# Hall_sensor.net
KiCad netlist of a schematic drawn in Altium Designer
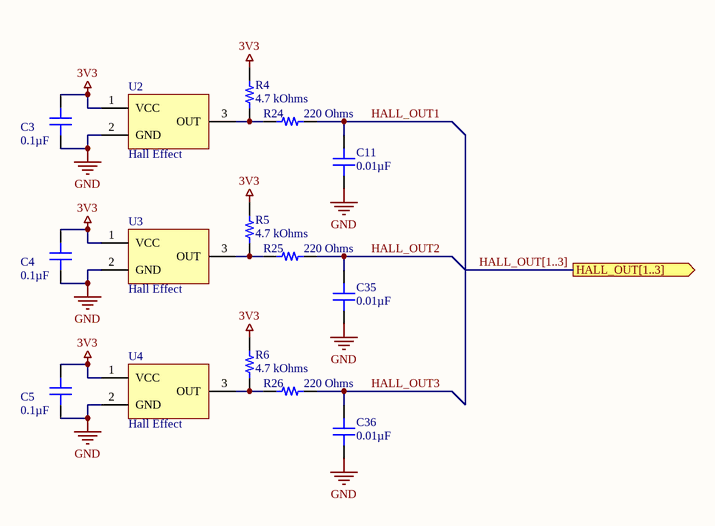
[diagram p0: Hall_sensor.SchDoc]

(export (version "E")
  (design (tool "Eeschema 10.0.6"))
  (components
    (comp (ref "C3")
      (value "0.1µF")
      (footprint "CAP 0603_1608")
      (description "CAP CER 0.1UF 100V 0603 EPOXY")
      (fields
        (field (name "PART NUMBER") "GCG188R92A104KA03D")
        (field (name "MANUFACTURER") "Murata Electronics")
      )
      (libsource (lib "Celestial Altium Library - altium_library") (part "Capacitor"))
    )
    (comp (ref "C4")
      (value "0.1µF")
      (footprint "CAP 0603_1608")
      (description "CAP CER 0.1UF 100V 0603 EPOXY")
      (fields
        (field (name "PART NUMBER") "GCG188R92A104KA03D")
        (field (name "MANUFACTURER") "Murata Electronics")
      )
      (libsource (lib "Celestial Altium Library - altium_library") (part "Capacitor"))
    )
    (comp (ref "C5")
      (value "0.1µF")
      (footprint "CAP 0603_1608")
      (description "CAP CER 0.1UF 100V 0603 EPOXY")
      (fields
        (field (name "PART NUMBER") "GCG188R92A104KA03D")
        (field (name "MANUFACTURER") "Murata Electronics")
      )
      (libsource (lib "Celestial Altium Library - altium_library") (part "Capacitor"))
    )
    (comp (ref "C11")
      (value "0.01µF")
      (footprint "CAP 0603_1608")
      (description "CAP CER 0.01UF 250V X7R 0603")
      (fields (field (name "PART NUMBER") "C0603C103KARACAUTO") (field (name "MANUFACTURER") "KEMET"))
      (libsource (lib "Celestial Altium Library - altium_library") (part "Capacitor"))
    )
    (comp (ref "C35")
      (value "0.01µF")
      (footprint "CAP 0603_1608")
      (description "CAP CER 0.01UF 250V X7R 0603")
      (fields (field (name "PART NUMBER") "C0603C103KARACAUTO") (field (name "MANUFACTURER") "KEMET"))
      (libsource (lib "Celestial Altium Library - altium_library") (part "Capacitor"))
    )
    (comp (ref "C36")
      (value "0.01µF")
      (footprint "CAP 0603_1608")
      (description "CAP CER 0.01UF 250V X7R 0603")
      (fields (field (name "PART NUMBER") "C0603C103KARACAUTO") (field (name "MANUFACTURER") "KEMET"))
      (libsource (lib "Celestial Altium Library - altium_library") (part "Capacitor"))
    )
    (comp (ref "R4")
      (value "4.7 kOhms")
      (footprint "RES 0603_1608")
      (description "RES SMD 4.7K OHM 1% 1/10W 0603")
      (fields (field (name "PART NUMBER") "CRCW06034K70FKTA") (field (name "MANUFACTURER") "Vishay Dale"))
      (libsource (lib "Celestial Altium Library - altium_library") (part "Resistor"))
    )
    (comp (ref "R5")
      (value "4.7 kOhms")
      (footprint "RES 0603_1608")
      (description "RES SMD 4.7K OHM 1% 1/10W 0603")
      (fields (field (name "PART NUMBER") "CRCW06034K70FKTA") (field (name "MANUFACTURER") "Vishay Dale"))
      (libsource (lib "Celestial Altium Library - altium_library") (part "Resistor"))
    )
    (comp (ref "R6")
      (value "4.7 kOhms")
      (footprint "RES 0603_1608")
      (description "RES SMD 4.7K OHM 1% 1/10W 0603")
      (fields (field (name "PART NUMBER") "CRCW06034K70FKTA") (field (name "MANUFACTURER") "Vishay Dale"))
      (libsource (lib "Celestial Altium Library - altium_library") (part "Resistor"))
    )
    (comp (ref "R24")
      (value "220 Ohms")
      (footprint "RES 0603_1608")
      (description "RES SMD 220 OHM 5% 0.3W 0603")
      (fields (field (name "PART NUMBER") "SDR03EZPJ221") (field (name "MANUFACTURER") "Rohm Semiconductor"))
      (libsource (lib "Celestial Altium Library - altium_library") (part "Resistor"))
    )
    (comp (ref "R25")
      (value "220 Ohms")
      (footprint "RES 0603_1608")
      (description "RES SMD 220 OHM 5% 0.3W 0603")
      (fields (field (name "PART NUMBER") "SDR03EZPJ221") (field (name "MANUFACTURER") "Rohm Semiconductor"))
      (libsource (lib "Celestial Altium Library - altium_library") (part "Resistor"))
    )
    (comp (ref "R26")
      (value "220 Ohms")
      (footprint "RES 0603_1608")
      (description "RES SMD 220 OHM 5% 0.3W 0603")
      (fields (field (name "PART NUMBER") "SDR03EZPJ221") (field (name "MANUFACTURER") "Rohm Semiconductor"))
      (libsource (lib "Celestial Altium Library - altium_library") (part "Resistor"))
    )
    (comp (ref "U2") (value "Hall Effect") (footprint "DRV5011ADLPG") (libsource (lib "IC") (part "DRV5011")))
    (comp (ref "U3") (value "Hall Effect") (footprint "DRV5011ADLPG") (libsource (lib "IC") (part "DRV5011")))
    (comp (ref "U4") (value "Hall Effect") (footprint "DRV5011ADLPG") (libsource (lib "IC") (part "DRV5011")))
  )
  (nets
    (net (code "1") (name "/HALL_OUT1") (class "Default")
      (node (ref "C11") (pin "2") (pinfunction "2_2") (pintype "passive"))
      (node (ref "R24") (pin "2") (pinfunction "2_2") (pintype "passive"))
    )
    (net (code "2") (name "/HALL_OUT2") (class "Default")
      (node (ref "C35") (pin "2") (pinfunction "2_2") (pintype "passive"))
      (node (ref "R25") (pin "2") (pinfunction "2_2") (pintype "passive"))
    )
    (net (code "3") (name "/HALL_OUT3") (class "Default")
      (node (ref "C36") (pin "2") (pinfunction "2_2") (pintype "passive"))
      (node (ref "R26") (pin "2") (pinfunction "2_2") (pintype "passive"))
    )
    (net (code "5") (name "3V3") (class "Default")
      (node (ref "C3") (pin "1") (pinfunction "1_1") (pintype "passive"))
      (node (ref "C4") (pin "1") (pinfunction "1_1") (pintype "passive"))
      (node (ref "C5") (pin "1") (pinfunction "1_1") (pintype "passive"))
      (node (ref "R4") (pin "2") (pinfunction "2_2") (pintype "passive"))
      (node (ref "R5") (pin "1") (pinfunction "1_1") (pintype "passive"))
      (node (ref "R6") (pin "1") (pinfunction "1_1") (pintype "passive"))
      (node (ref "U2") (pin "1") (pinfunction "VCC_1") (pintype "passive"))
      (node (ref "U3") (pin "1") (pinfunction "VCC_1") (pintype "passive"))
      (node (ref "U4") (pin "1") (pinfunction "VCC_1") (pintype "passive"))
    )
    (net (code "6") (name "GND") (class "Default")
      (node (ref "C11") (pin "1") (pinfunction "1_1") (pintype "passive"))
      (node (ref "C3") (pin "2") (pinfunction "2_2") (pintype "passive"))
      (node (ref "C35") (pin "1") (pinfunction "1_1") (pintype "passive"))
      (node (ref "C36") (pin "1") (pinfunction "1_1") (pintype "passive"))
      (node (ref "C4") (pin "2") (pinfunction "2_2") (pintype "passive"))
      (node (ref "C5") (pin "2") (pinfunction "2_2") (pintype "passive"))
      (node (ref "U2") (pin "2") (pinfunction "GND_2") (pintype "passive"))
      (node (ref "U3") (pin "2") (pinfunction "GND_2") (pintype "passive"))
      (node (ref "U4") (pin "2") (pinfunction "GND_2") (pintype "passive"))
    )
    (net (code "7") (name "Net-(U2-OUT)") (class "Default")
      (node (ref "R24") (pin "1") (pinfunction "1_1") (pintype "passive"))
      (node (ref "R4") (pin "1") (pinfunction "1_1") (pintype "passive"))
      (node (ref "U2") (pin "3") (pinfunction "OUT_3") (pintype "passive"))
    )
    (net (code "8") (name "Net-(U3-OUT)") (class "Default")
      (node (ref "R25") (pin "1") (pinfunction "1_1") (pintype "passive"))
      (node (ref "R5") (pin "2") (pinfunction "2_2") (pintype "passive"))
      (node (ref "U3") (pin "3") (pinfunction "OUT_3") (pintype "passive"))
    )
    (net (code "9") (name "Net-(U4-OUT)") (class "Default")
      (node (ref "R26") (pin "1") (pinfunction "1_1") (pintype "passive"))
      (node (ref "R6") (pin "2") (pinfunction "2_2") (pintype "passive"))
      (node (ref "U4") (pin "3") (pinfunction "OUT_3") (pintype "passive"))
    )
  )
)
